# W700A.net
KiCad netlist of a schematic drawn in EAGLE
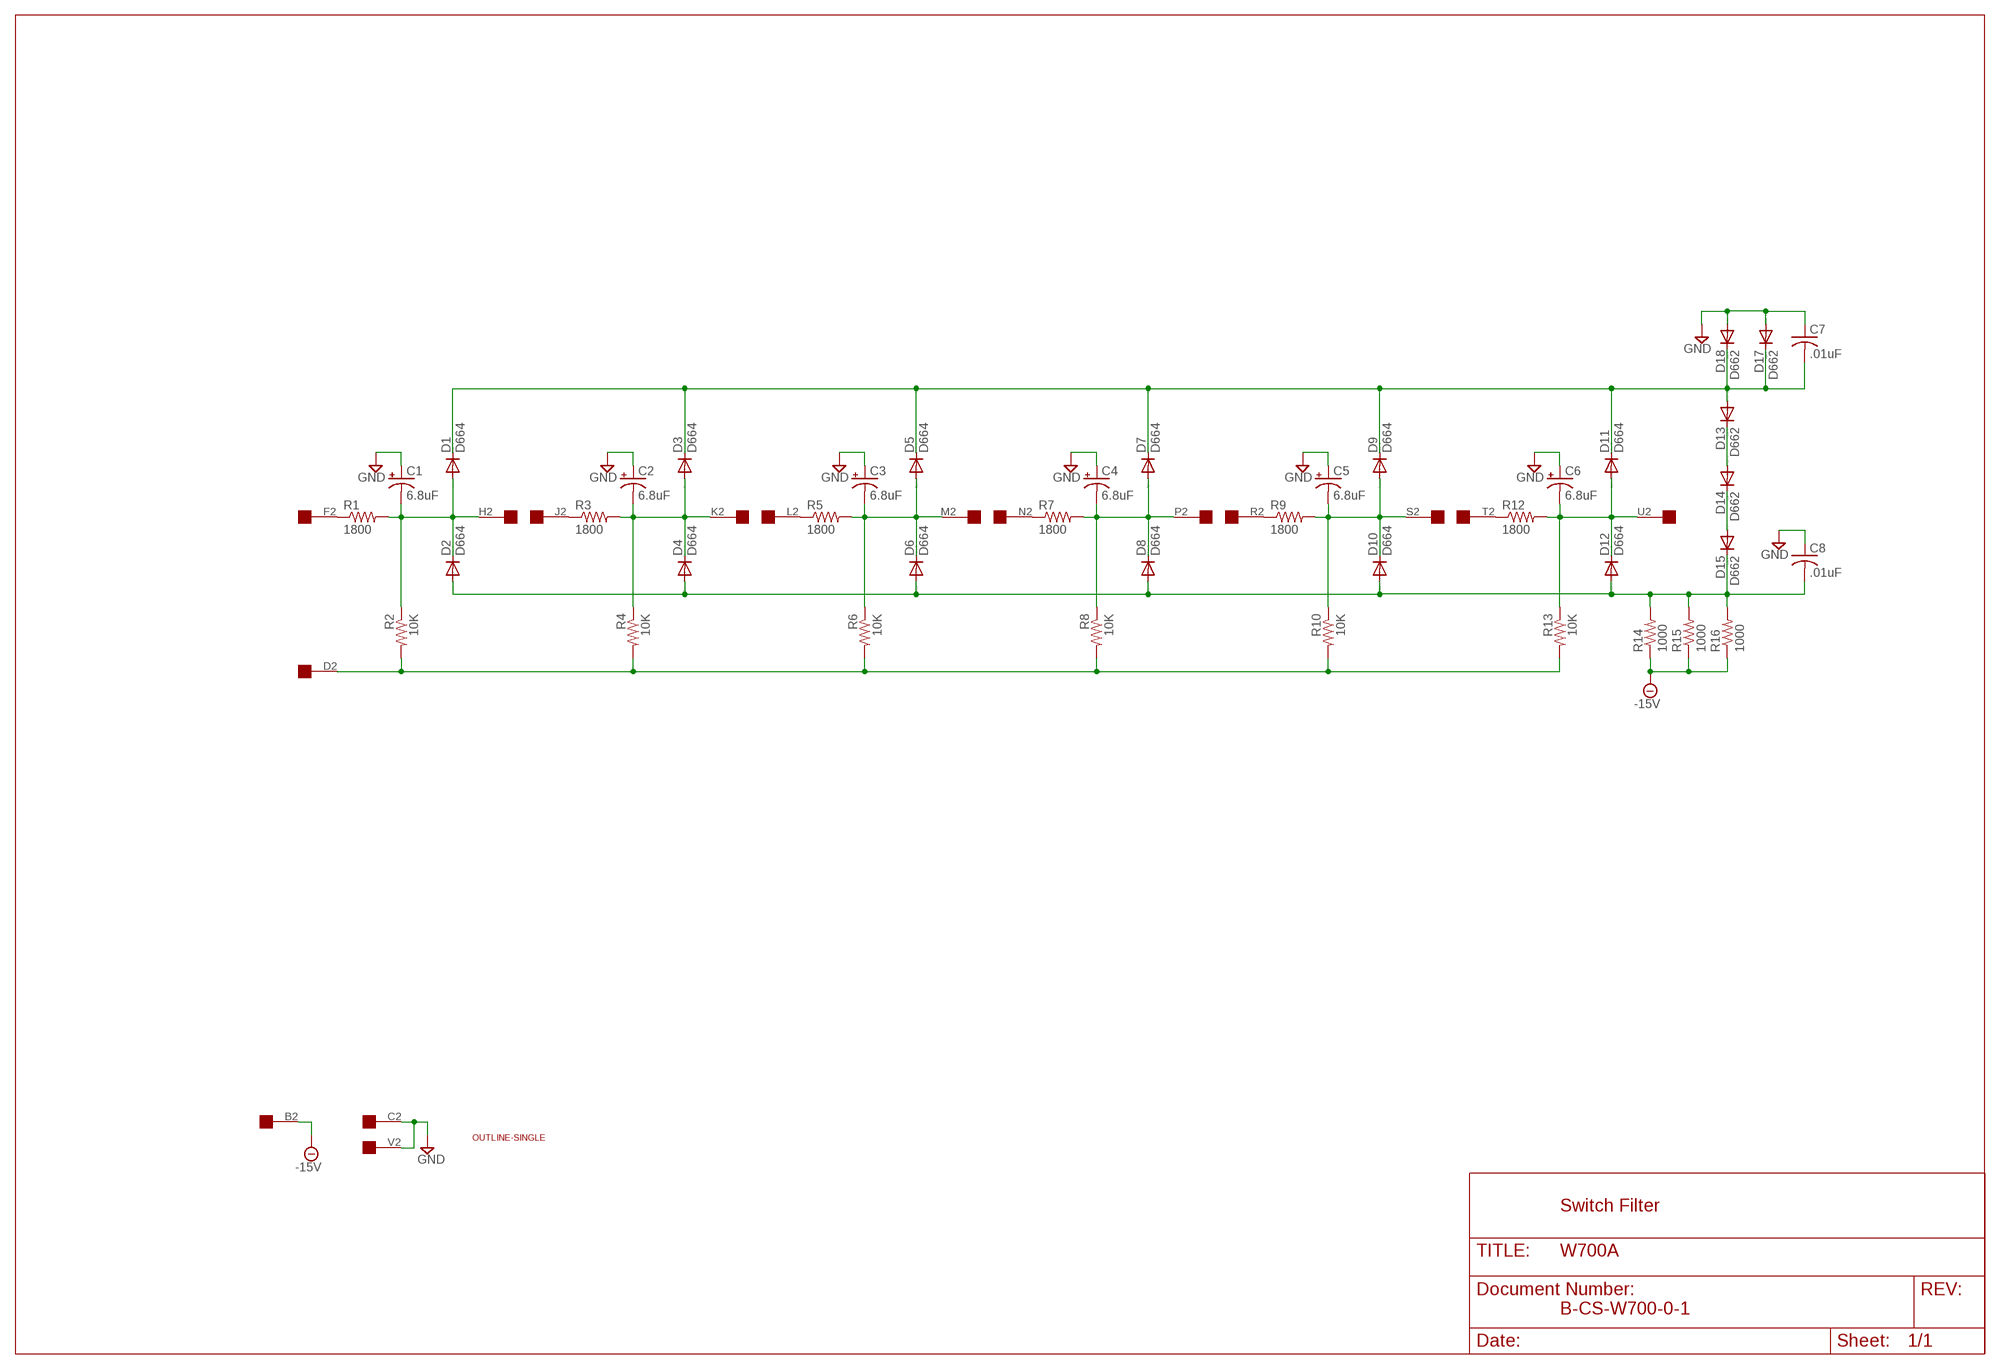
[diagram p0: schematic, sheet 1]

(export (version "E")
  (design (tool "Eeschema 10.0.6"))
  (components
    (comp (ref "C1")
      (value "6.8uF")
      (footprint "eagle-import:E15-5")
      (libsource (lib "eagle-import") (part "CPOL-USE15-5AXIAL"))
    )
    (comp (ref "C2")
      (value "6.8uF")
      (footprint "eagle-import:E15-5")
      (libsource (lib "eagle-import") (part "CPOL-USE15-5AXIAL"))
    )
    (comp (ref "C3")
      (value "6.8uF")
      (footprint "eagle-import:E15-5")
      (libsource (lib "eagle-import") (part "CPOL-USE15-5AXIAL"))
    )
    (comp (ref "C4")
      (value "6.8uF")
      (footprint "eagle-import:E15-5")
      (libsource (lib "eagle-import") (part "CPOL-USE15-5AXIAL"))
    )
    (comp (ref "C5")
      (value "6.8uF")
      (footprint "eagle-import:E15-5")
      (libsource (lib "eagle-import") (part "CPOL-USE15-5AXIAL"))
    )
    (comp (ref "C6")
      (value "6.8uF")
      (footprint "eagle-import:E15-5")
      (libsource (lib "eagle-import") (part "CPOL-USE15-5AXIAL"))
    )
    (comp (ref "C7")
      (value ".01uF")
      (footprint "eagle-import:C050-025X075")
      (libsource (lib "eagle-import") (part "C-US050-025X075"))
    )
    (comp (ref "C8")
      (value ".01uF")
      (footprint "eagle-import:C050-025X075")
      (libsource (lib "eagle-import") (part "C-US050-025X075"))
    )
    (comp (ref "D1")
      (value "D664")
      (footprint "eagle-import:DO35-10")
      (libsource (lib "eagle-import") (part "DIODE-DO35-10"))
    )
    (comp (ref "D2")
      (value "D664")
      (footprint "eagle-import:DO35-10")
      (libsource (lib "eagle-import") (part "DIODE-DO35-10"))
    )
    (comp (ref "D3")
      (value "D664")
      (footprint "eagle-import:DO35-10")
      (libsource (lib "eagle-import") (part "DIODE-DO35-10"))
    )
    (comp (ref "D4")
      (value "D664")
      (footprint "eagle-import:DO35-10")
      (libsource (lib "eagle-import") (part "DIODE-DO35-10"))
    )
    (comp (ref "D5")
      (value "D664")
      (footprint "eagle-import:DO35-10")
      (libsource (lib "eagle-import") (part "DIODE-DO35-10"))
    )
    (comp (ref "D6")
      (value "D664")
      (footprint "eagle-import:DO35-10")
      (libsource (lib "eagle-import") (part "DIODE-DO35-10"))
    )
    (comp (ref "D7")
      (value "D664")
      (footprint "eagle-import:DO35-10")
      (libsource (lib "eagle-import") (part "DIODE-DO35-10"))
    )
    (comp (ref "D8")
      (value "D664")
      (footprint "eagle-import:DO35-10")
      (libsource (lib "eagle-import") (part "DIODE-DO35-10"))
    )
    (comp (ref "D9")
      (value "D664")
      (footprint "eagle-import:DO35-10")
      (libsource (lib "eagle-import") (part "DIODE-DO35-10"))
    )
    (comp (ref "D10")
      (value "D664")
      (footprint "eagle-import:DO35-10")
      (libsource (lib "eagle-import") (part "DIODE-DO35-10"))
    )
    (comp (ref "D11")
      (value "D664")
      (footprint "eagle-import:DO35-10")
      (libsource (lib "eagle-import") (part "DIODE-DO35-10"))
    )
    (comp (ref "D12")
      (value "D664")
      (footprint "eagle-import:DO35-10")
      (libsource (lib "eagle-import") (part "DIODE-DO35-10"))
    )
    (comp (ref "D13")
      (value "D662")
      (footprint "eagle-import:DO35-10")
      (libsource (lib "eagle-import") (part "DIODE-DO35-10"))
    )
    (comp (ref "D14")
      (value "D662")
      (footprint "eagle-import:DO35-10")
      (libsource (lib "eagle-import") (part "DIODE-DO35-10"))
    )
    (comp (ref "D15")
      (value "D662")
      (footprint "eagle-import:DO35-10")
      (libsource (lib "eagle-import") (part "DIODE-DO35-10"))
    )
    (comp (ref "D17")
      (value "D662")
      (footprint "eagle-import:DO35-10")
      (libsource (lib "eagle-import") (part "DIODE-DO35-10"))
    )
    (comp (ref "D18")
      (value "D662")
      (footprint "eagle-import:DO35-10")
      (libsource (lib "eagle-import") (part "DIODE-DO35-10"))
    )
    (comp (ref "R1")
      (value "1800")
      (footprint "eagle-import:0207_10")
      (libsource (lib "eagle-import") (part "R-US_0207/10"))
    )
    (comp (ref "R2")
      (value "10K")
      (footprint "eagle-import:0207_10")
      (libsource (lib "eagle-import") (part "R-US_0207/10"))
    )
    (comp (ref "R3")
      (value "1800")
      (footprint "eagle-import:0207_10")
      (libsource (lib "eagle-import") (part "R-US_0207/10"))
    )
    (comp (ref "R4")
      (value "10K")
      (footprint "eagle-import:0207_10")
      (libsource (lib "eagle-import") (part "R-US_0207/10"))
    )
    (comp (ref "R5")
      (value "1800")
      (footprint "eagle-import:0207_10")
      (libsource (lib "eagle-import") (part "R-US_0207/10"))
    )
    (comp (ref "R6")
      (value "10K")
      (footprint "eagle-import:0207_10")
      (libsource (lib "eagle-import") (part "R-US_0207/10"))
    )
    (comp (ref "R7")
      (value "1800")
      (footprint "eagle-import:0207_10")
      (libsource (lib "eagle-import") (part "R-US_0207/10"))
    )
    (comp (ref "R8")
      (value "10K")
      (footprint "eagle-import:0207_10")
      (libsource (lib "eagle-import") (part "R-US_0207/10"))
    )
    (comp (ref "R9")
      (value "1800")
      (footprint "eagle-import:0207_10")
      (libsource (lib "eagle-import") (part "R-US_0207/10"))
    )
    (comp (ref "R10")
      (value "10K")
      (footprint "eagle-import:0207_10")
      (libsource (lib "eagle-import") (part "R-US_0207/10"))
    )
    (comp (ref "R12")
      (value "1800")
      (footprint "eagle-import:0207_10")
      (libsource (lib "eagle-import") (part "R-US_0207/10"))
    )
    (comp (ref "R13")
      (value "10K")
      (footprint "eagle-import:0207_10")
      (libsource (lib "eagle-import") (part "R-US_0207/10"))
    )
    (comp (ref "R14")
      (value "1000")
      (footprint "eagle-import:0207_10")
      (libsource (lib "eagle-import") (part "R-US_0207/10"))
    )
    (comp (ref "R15")
      (value "1000")
      (footprint "eagle-import:0207_10")
      (libsource (lib "eagle-import") (part "R-US_0207/10"))
    )
    (comp (ref "R16")
      (value "1000")
      (footprint "eagle-import:0207_10")
      (libsource (lib "eagle-import") (part "R-US_0207/10"))
    )
    (comp (ref "U$1")
      (value "OUTLINE-SINGLE")
      (footprint "eagle-import:SINGLE")
      (libsource (lib "eagle-import") (part "OUTLINE-SINGLE"))
    )
    (comp (ref "U$3")
      (value "EDGE-1")
      (footprint "eagle-import:EDGE-CON1")
      (libsource (lib "eagle-import") (part "EDGE-1"))
    )
  )
  (nets
    (net (code "1") (name "-15V") (class "Default")
      (node (ref "R14") (pin "1") (pinfunction "1_1") (pintype "passive"))
      (node (ref "R15") (pin "1") (pinfunction "1_1") (pintype "passive"))
      (node (ref "R16") (pin "1") (pinfunction "1_1") (pintype "passive"))
      (node (ref "U$3") (pin "B2") (pinfunction "1_B2") (pintype "bidirectional"))
    )
    (net (code "2") (name "GND") (class "Default")
      (node (ref "C1") (pin "+") (pinfunction "+_+") (pintype "passive"))
      (node (ref "C2") (pin "+") (pinfunction "+_+") (pintype "passive"))
      (node (ref "C3") (pin "+") (pinfunction "+_+") (pintype "passive"))
      (node (ref "C4") (pin "+") (pinfunction "+_+") (pintype "passive"))
      (node (ref "C5") (pin "+") (pinfunction "+_+") (pintype "passive"))
      (node (ref "C6") (pin "+") (pinfunction "+_+") (pintype "passive"))
      (node (ref "C7") (pin "1") (pinfunction "1_1") (pintype "passive"))
      (node (ref "C8") (pin "1") (pinfunction "1_1") (pintype "passive"))
      (node (ref "D17") (pin "A") (pinfunction "A_A") (pintype "passive"))
      (node (ref "D18") (pin "A") (pinfunction "A_A") (pintype "passive"))
      (node (ref "U$3") (pin "C2") (pinfunction "1_C2") (pintype "bidirectional"))
      (node (ref "U$3") (pin "V2") (pinfunction "1_V2") (pintype "bidirectional"))
    )
    (net (code "3") (name "Net-(C7-Pad2)") (class "Default")
      (node (ref "C7") (pin "2") (pinfunction "2_2") (pintype "passive"))
      (node (ref "D1") (pin "C") (pinfunction "C_C") (pintype "passive"))
      (node (ref "D11") (pin "C") (pinfunction "C_C") (pintype "passive"))
      (node (ref "D13") (pin "A") (pinfunction "A_A") (pintype "passive"))
      (node (ref "D17") (pin "C") (pinfunction "C_C") (pintype "passive"))
      (node (ref "D18") (pin "C") (pinfunction "C_C") (pintype "passive"))
      (node (ref "D3") (pin "C") (pinfunction "C_C") (pintype "passive"))
      (node (ref "D5") (pin "C") (pinfunction "C_C") (pintype "passive"))
      (node (ref "D7") (pin "C") (pinfunction "C_C") (pintype "passive"))
      (node (ref "D9") (pin "C") (pinfunction "C_C") (pintype "passive"))
    )
    (net (code "4") (name "Net-(C8-Pad2)") (class "Default")
      (node (ref "C8") (pin "2") (pinfunction "2_2") (pintype "passive"))
      (node (ref "D10") (pin "A") (pinfunction "A_A") (pintype "passive"))
      (node (ref "D12") (pin "A") (pinfunction "A_A") (pintype "passive"))
      (node (ref "D15") (pin "C") (pinfunction "C_C") (pintype "passive"))
      (node (ref "D2") (pin "A") (pinfunction "A_A") (pintype "passive"))
      (node (ref "D4") (pin "A") (pinfunction "A_A") (pintype "passive"))
      (node (ref "D6") (pin "A") (pinfunction "A_A") (pintype "passive"))
      (node (ref "D8") (pin "A") (pinfunction "A_A") (pintype "passive"))
      (node (ref "R14") (pin "2") (pinfunction "2_2") (pintype "passive"))
      (node (ref "R15") (pin "2") (pinfunction "2_2") (pintype "passive"))
      (node (ref "R16") (pin "2") (pinfunction "2_2") (pintype "passive"))
    )
    (net (code "5") (name "Net-(D13-PadC)") (class "Default")
      (node (ref "D13") (pin "C") (pinfunction "C_C") (pintype "passive"))
      (node (ref "D14") (pin "A") (pinfunction "A_A") (pintype "passive"))
    )
    (net (code "6") (name "Net-(D14-PadC)") (class "Default")
      (node (ref "D14") (pin "C") (pinfunction "C_C") (pintype "passive"))
      (node (ref "D15") (pin "A") (pinfunction "A_A") (pintype "passive"))
    )
    (net (code "7") (name "Net-(U$3D-1)") (class "Default")
      (node (ref "R10") (pin "2") (pinfunction "2_2") (pintype "passive"))
      (node (ref "R13") (pin "2") (pinfunction "2_2") (pintype "passive"))
      (node (ref "R2") (pin "2") (pinfunction "2_2") (pintype "passive"))
      (node (ref "R4") (pin "2") (pinfunction "2_2") (pintype "passive"))
      (node (ref "R6") (pin "2") (pinfunction "2_2") (pintype "passive"))
      (node (ref "R8") (pin "2") (pinfunction "2_2") (pintype "passive"))
      (node (ref "U$3") (pin "D2") (pinfunction "1_D2") (pintype "bidirectional"))
    )
    (net (code "8") (name "Net-(U$3F-1)") (class "Default")
      (node (ref "R1") (pin "1") (pinfunction "1_1") (pintype "passive"))
      (node (ref "U$3") (pin "F2") (pinfunction "1_F2") (pintype "bidirectional"))
    )
    (net (code "9") (name "Net-(U$3G-1)") (class "Default")
      (node (ref "C1") (pin "-") (pinfunction "-_-") (pintype "passive"))
      (node (ref "D1") (pin "A") (pinfunction "A_A") (pintype "passive"))
      (node (ref "D2") (pin "C") (pinfunction "C_C") (pintype "passive"))
      (node (ref "R1") (pin "2") (pinfunction "2_2") (pintype "passive"))
      (node (ref "R2") (pin "1") (pinfunction "1_1") (pintype "passive"))
      (node (ref "U$3") (pin "H2") (pinfunction "1_H2") (pintype "bidirectional"))
    )
    (net (code "10") (name "Net-(U$3H-1)") (class "Default")
      (node (ref "R3") (pin "1") (pinfunction "1_1") (pintype "passive"))
      (node (ref "U$3") (pin "J2") (pinfunction "1_J2") (pintype "bidirectional"))
    )
    (net (code "11") (name "Net-(U$3I-1)") (class "Default")
      (node (ref "C2") (pin "-") (pinfunction "-_-") (pintype "passive"))
      (node (ref "D3") (pin "A") (pinfunction "A_A") (pintype "passive"))
      (node (ref "D4") (pin "C") (pinfunction "C_C") (pintype "passive"))
      (node (ref "R3") (pin "2") (pinfunction "2_2") (pintype "passive"))
      (node (ref "R4") (pin "1") (pinfunction "1_1") (pintype "passive"))
      (node (ref "U$3") (pin "K2") (pinfunction "1_K2") (pintype "bidirectional"))
    )
    (net (code "12") (name "Net-(U$3J-1)") (class "Default")
      (node (ref "R5") (pin "1") (pinfunction "1_1") (pintype "passive"))
      (node (ref "U$3") (pin "L2") (pinfunction "1_L2") (pintype "bidirectional"))
    )
    (net (code "13") (name "Net-(U$3K-1)") (class "Default")
      (node (ref "C3") (pin "-") (pinfunction "-_-") (pintype "passive"))
      (node (ref "D5") (pin "A") (pinfunction "A_A") (pintype "passive"))
      (node (ref "D6") (pin "C") (pinfunction "C_C") (pintype "passive"))
      (node (ref "R5") (pin "2") (pinfunction "2_2") (pintype "passive"))
      (node (ref "R6") (pin "1") (pinfunction "1_1") (pintype "passive"))
      (node (ref "U$3") (pin "M2") (pinfunction "1_M2") (pintype "bidirectional"))
    )
    (net (code "14") (name "Net-(U$3L-1)") (class "Default")
      (node (ref "R7") (pin "1") (pinfunction "1_1") (pintype "passive"))
      (node (ref "U$3") (pin "N2") (pinfunction "1_N2") (pintype "bidirectional"))
    )
    (net (code "15") (name "Net-(U$3M-1)") (class "Default")
      (node (ref "C4") (pin "-") (pinfunction "-_-") (pintype "passive"))
      (node (ref "D7") (pin "A") (pinfunction "A_A") (pintype "passive"))
      (node (ref "D8") (pin "C") (pinfunction "C_C") (pintype "passive"))
      (node (ref "R7") (pin "2") (pinfunction "2_2") (pintype "passive"))
      (node (ref "R8") (pin "1") (pinfunction "1_1") (pintype "passive"))
      (node (ref "U$3") (pin "P2") (pinfunction "1_P2") (pintype "bidirectional"))
    )
    (net (code "16") (name "Net-(U$3N-1)") (class "Default")
      (node (ref "R9") (pin "1") (pinfunction "1_1") (pintype "passive"))
      (node (ref "U$3") (pin "R2") (pinfunction "1_R2") (pintype "bidirectional"))
    )
    (net (code "17") (name "Net-(U$3O-1)") (class "Default")
      (node (ref "C5") (pin "-") (pinfunction "-_-") (pintype "passive"))
      (node (ref "D10") (pin "C") (pinfunction "C_C") (pintype "passive"))
      (node (ref "D9") (pin "A") (pinfunction "A_A") (pintype "passive"))
      (node (ref "R10") (pin "1") (pinfunction "1_1") (pintype "passive"))
      (node (ref "R9") (pin "2") (pinfunction "2_2") (pintype "passive"))
      (node (ref "U$3") (pin "S2") (pinfunction "1_S2") (pintype "bidirectional"))
    )
    (net (code "18") (name "Net-(U$3P-1)") (class "Default")
      (node (ref "R12") (pin "1") (pinfunction "1_1") (pintype "passive"))
      (node (ref "U$3") (pin "T2") (pinfunction "1_T2") (pintype "bidirectional"))
    )
    (net (code "19") (name "Net-(U$3Q-1)") (class "Default")
      (node (ref "C6") (pin "-") (pinfunction "-_-") (pintype "passive"))
      (node (ref "D11") (pin "A") (pinfunction "A_A") (pintype "passive"))
      (node (ref "D12") (pin "C") (pinfunction "C_C") (pintype "passive"))
      (node (ref "R12") (pin "2") (pinfunction "2_2") (pintype "passive"))
      (node (ref "R13") (pin "1") (pinfunction "1_1") (pintype "passive"))
      (node (ref "U$3") (pin "U2") (pinfunction "1_U2") (pintype "bidirectional"))
    )
  )
)
